# design.net
KiCad netlist of a schematic drawn in Altium Designer
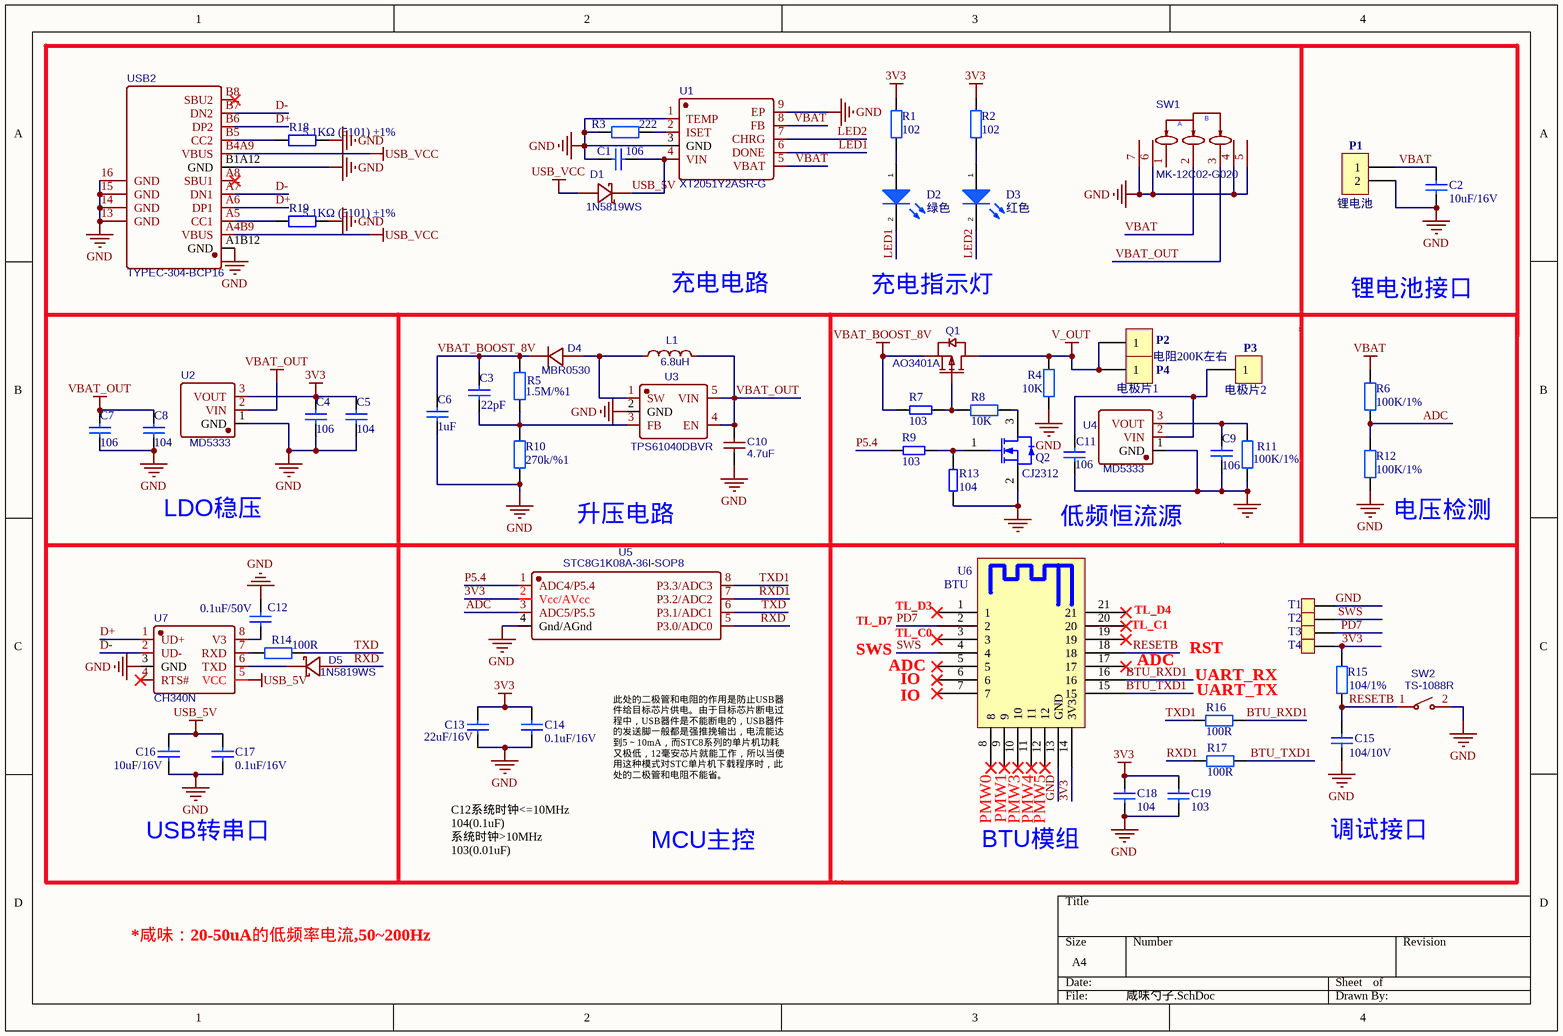
[diagram p0: 咸味勺子.SchDoc]

(export (version "E")
  (design (tool "Eeschema 10.0.6"))
  (components
    (comp (ref "C1")
      (value "106")
      (footprint "C0603")
      (description "无极性电容")
      (fields (field (name "PART NUMBER") "1.02.03.00181") (field (name "修改人") "system"))
      (libsource (lib "Database_Libs") (part "Capacitor - non polarized"))
    )
    (comp (ref "C2")
      (value "10uF/16V")
      (footprint "C0603")
      (description "无极性电容")
      (fields (field (name "PART NUMBER") "1.02.05.00869"))
      (libsource (lib "Database_Libs4") (part "Capacitor - non polarized"))
    )
    (comp (ref "C3")
      (value "22pF")
      (footprint "C0402_GRM15")
      (description "无极性电容")
      (fields (field (name "PART NUMBER") "1.02.05.00869"))
      (libsource (lib "Database_Libs4") (part "Capacitor - non polarized"))
    )
    (comp (ref "C4")
      (value "106")
      (footprint "C0603")
      (description "无极性电容")
      (fields (field (name "PART NUMBER") "1.02.05.00869"))
      (libsource (lib "Database_Libs4") (part "Capacitor - non polarized"))
    )
    (comp (ref "C5")
      (value "104")
      (footprint "C0402_GRM15")
      (description "无极性电容")
      (fields (field (name "PART NUMBER") "1.02.05.00869"))
      (libsource (lib "Database_Libs4") (part "Capacitor - non polarized"))
    )
    (comp (ref "C6")
      (value "1uF")
      (footprint "C0603")
      (description "无极性电容")
      (fields (field (name "PART NUMBER") "1.02.05.00869"))
      (libsource (lib "Database_Libs4") (part "Capacitor - non polarized"))
    )
    (comp (ref "C7")
      (value "106")
      (footprint "C0603")
      (description "无极性电容")
      (fields (field (name "PART NUMBER") "1.02.05.00869"))
      (libsource (lib "Database_Libs4") (part "Capacitor - non polarized"))
    )
    (comp (ref "C8")
      (value "104")
      (footprint "C0402_GRM15")
      (description "无极性电容")
      (fields (field (name "PART NUMBER") "1.02.05.00869"))
      (libsource (lib "Database_Libs4") (part "Capacitor - non polarized"))
    )
    (comp (ref "C9")
      (value "106")
      (footprint "C0603")
      (description "无极性电容")
      (fields (field (name "PART NUMBER") "1.02.05.00869"))
      (libsource (lib "Database_Libs4") (part "Capacitor - non polarized"))
    )
    (comp (ref "C10")
      (value "4.7uF")
      (footprint "JMK212BJ475KG-T")
      (fields
        (field (name "BOM_MANUFACTURER PART") "JMK212BJ475KG-T")
        (field (name "BOM_SUPPLIER PART") "C92788")
      )
      (libsource (lib "altium-import") (part "root_1_4.7uF_"))
    )
    (comp (ref "C11")
      (value "106")
      (footprint "C0603")
      (description "无极性电容")
      (fields (field (name "PART NUMBER") "1.02.05.00869"))
      (libsource (lib "Database_Libs4") (part "Capacitor - non polarized"))
    )
    (comp (ref "C12")
      (value "0.1uF/50V")
      (footprint "C0402_GRM15")
      (description "无极性电容")
      (fields (field (name "PART NUMBER") "1.02.05.00834") (field (name "修改人") "system"))
      (libsource (lib "Database_Libs") (part "Capacitor - non polarized"))
    )
    (comp (ref "C13")
      (value "22uF/16V")
      (footprint "C0603")
      (description "无极性电容")
      (fields (field (name "PART NUMBER") "1.02.03.00181") (field (name "修改人") "system"))
      (libsource (lib "Database_Libs") (part "Capacitor - non polarized"))
    )
    (comp (ref "C14")
      (value "0.1uF/16V")
      (footprint "C0402_GRM15")
      (description "无极性电容")
      (fields (field (name "PART NUMBER") "1.02.05.00834") (field (name "修改人") "system"))
      (libsource (lib "Database_Libs") (part "Capacitor - non polarized"))
    )
    (comp (ref "C15")
      (value "104/10V")
      (footprint "C0402_GRM15")
      (description "无极性电容")
      (fields (field (name "PART NUMBER") "1.02.05.00869"))
      (libsource (lib "Database_Libs4") (part "Capacitor - non polarized"))
    )
    (comp (ref "C16")
      (value "10uF/16V")
      (footprint "C0603")
      (description "无极性电容")
      (fields (field (name "PART NUMBER") "1.02.03.00181") (field (name "修改人") "system"))
      (libsource (lib "Database_Libs") (part "Capacitor - non polarized"))
    )
    (comp (ref "C17")
      (value "0.1uF/16V")
      (footprint "C0402_GRM15")
      (description "无极性电容")
      (fields (field (name "PART NUMBER") "1.02.05.00834") (field (name "修改人") "system"))
      (libsource (lib "Database_Libs") (part "Capacitor - non polarized"))
    )
    (comp (ref "C18")
      (value "104")
      (footprint "C0402_GRM15")
      (description "无极性电容")
      (fields (field (name "PART NUMBER") "1.02.05.00869"))
      (libsource (lib "Database_Libs4") (part "Capacitor - non polarized"))
    )
    (comp (ref "C19")
      (value "103")
      (footprint "C0402_GRM15")
      (description "无极性电容")
      (fields (field (name "PART NUMBER") "1.02.05.00869"))
      (libsource (lib "Database_Libs4") (part "Capacitor - non polarized"))
    )
    (comp (ref "D1")
      (value "1N5819WS")
      (footprint "1N5819WS")
      (fields (field (name "BOM_SUPPLIER PART") "C1884554") (field (name "CONTRIBUTOR") "LCSC"))
      (libsource (lib "altium-import") (part "root_2_1N5819WS_C1884554_"))
    )
    (comp (ref "D2")
      (value "绿色")
      (footprint "OSR50603C1E")
      (description "LED")
      (fields (field (name "PART NUMBER") "1.06.02.00452"))
      (libsource (lib "Database_Libs4") (part "LED"))
    )
    (comp (ref "D3")
      (value "红色")
      (footprint "OSR50603C1E")
      (description "LED")
      (fields (field (name "PART NUMBER") "1.06.02.00452"))
      (libsource (lib "Database_Libs4") (part "LED"))
    )
    (comp (ref "D4")
      (value "MBR0530")
      (footprint "MBR0530")
      (fields (field (name "BOM_SUPPLIER PART") "C475718") (field (name "CONTRIBUTOR") "LCSC"))
      (libsource (lib "altium-import") (part "root_0_MBR0530_C475718_"))
    )
    (comp (ref "D5")
      (value "1N5819WS")
      (footprint "SOD-323")
      (fields (field (name "BOM_SUPPLIER PART") "C1884554") (field (name "CONTRIBUTOR") "LCSC"))
      (libsource (lib "altium-import") (part "root_0_1N5819WS_C1884554_"))
    )
    (comp (ref "L1")
      (value "6.8uH")
      (footprint "CDRH3D23NP-6R8PC")
      (fields
        (field (name "BOM_SUPPLIER PART") "C323532")
        (field (name "BOM_MANUFACTURER PART") "CDRH3D23NP-6R8PC")
        (field (name "CONTRIBUTOR") "LCSC")
      )
      (libsource (lib "altium-import") (part "root_0_6.8uH_"))
    )
    (comp (ref "P1")
      (value "锂电池")
      (footprint "1.5mm 2p接插件")
      (description "Connector")
      (libsource (lib "*") (part "CON2"))
    )
    (comp (ref "P2") (value "CON1") (footprint "焊点1") (libsource (lib "智能烧水壶 -电源板") (part "CON1")))
    (comp (ref "P3") (value "CON1") (footprint "焊点1") (libsource (lib "智能烧水壶 -电源板") (part "CON1")))
    (comp (ref "P4") (value "CON1") (footprint "焊点1") (libsource (lib "智能烧水壶 -电源板") (part "CON1")))
    (comp (ref "Q1")
      (value "AO3401A")
      (footprint "AO3401A")
      (fields (field (name "BOM_SUPPLIER PART") "C700954") (field (name "CONTRIBUTOR") "LCSC"))
      (libsource (lib "altium-import") (part "root_1_mirrored_AO3401A_C700954_"))
    )
    (comp (ref "Q2")
      (value "CJ2312")
      (footprint "CJ2312")
      (description "N-Channel MOSFET")
      (fields
        (field (name "PART NUMBER") "1.06.11.00008")
        (field (name "ORCAD LIBRARY PATH") "‪Z:\\tuya_lib\\sch-lib\\DISCRETE.OLB")
        (field (name "修改人") "system")
      )
      (libsource (lib "Database_Libs") (part "MOSFET-N"))
    )
    (comp (ref "R1")
      (value "102")
      (footprint "R0402")
      (description "电阻")
      (fields (field (name "PART NUMBER") "1.01.01.00808"))
      (libsource (lib "Database_Libs4") (part "Resistor"))
    )
    (comp (ref "R2")
      (value "102")
      (footprint "R0402")
      (description "电阻")
      (fields (field (name "PART NUMBER") "1.01.01.00808"))
      (libsource (lib "Database_Libs4") (part "Resistor"))
    )
    (comp (ref "R3")
      (value "222")
      (footprint "R0402")
      (description "电阻")
      (fields (field (name "PART NUMBER") "1.01.01.00808"))
      (libsource (lib "") (part "Resistor_1"))
    )
    (comp (ref "R4")
      (value "10K")
      (footprint "R0402")
      (description "电阻")
      (libsource (lib "Database_Libs") (part "Resistor"))
    )
    (comp (ref "R5")
      (value "1.5M/%1")
      (footprint "R0402")
      (description "电阻")
      (libsource (lib "") (part "Resistor_1"))
    )
    (comp (ref "R6")
      (value "100K/1%")
      (footprint "R0402")
      (description "电阻")
      (libsource (lib "") (part "Resistor_1"))
    )
    (comp (ref "R7")
      (value "103")
      (footprint "R0402")
      (description "RES")
      (libsource (lib "先锋器件封装库") (part "RES-1"))
    )
    (comp (ref "R8")
      (value "10K")
      (footprint "R0402")
      (description "电阻")
      (libsource (lib "") (part "Resistor_2"))
    )
    (comp (ref "R9")
      (value "103")
      (footprint "R0402")
      (description "RES")
      (libsource (lib "先锋器件封装库") (part "RES-1"))
    )
    (comp (ref "R10")
      (value "270k/%1")
      (footprint "R0402")
      (description "电阻")
      (libsource (lib "") (part "Resistor_1"))
    )
    (comp (ref "R11")
      (value "100K/1%")
      (footprint "R0402")
      (description "电阻")
      (libsource (lib "") (part "Resistor_1"))
    )
    (comp (ref "R12")
      (value "100K/1%")
      (footprint "R0402")
      (description "电阻")
      (libsource (lib "") (part "Resistor_1"))
    )
    (comp (ref "R13")
      (value "104")
      (footprint "R0402")
      (description "RES")
      (libsource (lib "先锋器件封装库") (part "RES-1"))
    )
    (comp (ref "R14")
      (value "100R")
      (footprint "R0402")
      (description "电阻")
      (fields (field (name "PART NUMBER") "1.01.01.00808") (field (name "修改人") "system"))
      (libsource (lib "") (part "Resistor_2"))
    )
    (comp (ref "R15")
      (value "104/1%")
      (footprint "R0402")
      (description "电阻")
      (fields (field (name "PART NUMBER") "1.01.01.00808"))
      (libsource (lib "Database_Libs4") (part "Resistor"))
    )
    (comp (ref "R16")
      (value "100R")
      (footprint "R0402")
      (description "电阻")
      (fields (field (name "PART NUMBER") "1.01.01.00808"))
      (libsource (lib "") (part "Resistor_1"))
    )
    (comp (ref "R17")
      (value "100R")
      (footprint "R0402")
      (description "电阻")
      (fields (field (name "PART NUMBER") "1.01.01.00808"))
      (libsource (lib "") (part "Resistor_1"))
    )
    (comp (ref "R18")
      (value "5.1KΩ (5101) ±1%")
      (footprint "0603_R")
      (description "贴片电阻")
      (libsource (lib "Miscellaneous Devices LC") (part "0603 5.1KΩ (5101) 1%"))
    )
    (comp (ref "R19")
      (value "5.1KΩ (5101) ±1%")
      (footprint "0603_R")
      (description "贴片电阻")
      (libsource (lib "Miscellaneous Devices LC") (part "0603 5.1KΩ (5101) 1%"))
    )
    (comp (ref "SW1")
      (value "MK-12C02-G020")
      (footprint "SW-SMD_MK-12C02-G020")
      (fields (field (name "BOM_SUPPLIER PART") "C963206") (field (name "CONTRIBUTOR") "LCSC"))
      (libsource (lib "MYSCH") (part "SW-MK-12C02-G020"))
    )
    (comp (ref "SW2")
      (value "TS-1088R")
      (footprint "TS-1088R-02026")
      (fields
        (field (name "BOM_SUPPLIER PART") "C455280")
        (field (name "BOM_MANUFACTURER PART") "TS-1088R-02026")
        (field (name "CONTRIBUTOR") "LCSC")
      )
      (libsource (lib "altium-import") (part "root_0_TS-1088R-02026_"))
    )
    (comp (ref "T1") (value "TP") (footprint "TP1") (libsource (lib "MIAXIS-SCH") (part "TP")))
    (comp (ref "T2") (value "TP") (footprint "TP1") (libsource (lib "MIAXIS-SCH") (part "TP")))
    (comp (ref "T3") (value "TP") (footprint "TP1") (libsource (lib "MIAXIS-SCH") (part "TP")))
    (comp (ref "T4") (value "TP") (footprint "TP1") (libsource (lib "MIAXIS-SCH") (part "TP")))
    (comp (ref "U1")
      (value "XT2051Y2ASR-G")
      (footprint "XT2051Y2ASR-G")
      (fields (field (name "BOM_SUPPLIER PART") "C236398") (field (name "CONTRIBUTOR") "LCSC"))
      (libsource (lib "altium-import") (part "root_0_XT2051Y2ASR-G_"))
    )
    (comp (ref "U2")
      (value "MD5333")
      (footprint "MD5333")
      (fields (field (name "BOM_SUPPLIER PART") "C2827936") (field (name "CONTRIBUTOR") "LCSC"))
      (libsource (lib "altium-import") (part "root_2_MD5333_"))
    )
    (comp (ref "U3")
      (value "TPS61040DBVR")
      (footprint "TPS61040DBVR")
      (fields (field (name "BOM_SUPPLIER PART") "C7722"))
      (libsource (lib "altium-import") (part "root_0_TPS61040DBVR_"))
    )
    (comp (ref "U4")
      (value "MD5333")
      (footprint "MD5333")
      (fields (field (name "BOM_SUPPLIER PART") "C2827936") (field (name "CONTRIBUTOR") "LCSC"))
      (libsource (lib "altium-import") (part "root_2_MD5333_"))
    )
    (comp (ref "U5")
      (value "STC8G1K08A-36I-SOP8")
      (footprint "STC8G1K08A-36I-SOP8")
      (fields (field (name "BOM_SUPPLIER PART") "C915663") (field (name "CONTRIBUTOR") "LCSC"))
      (libsource (lib "altium-import") (part "root_0_STC8G1K08A-36I-SOP8_"))
    )
    (comp (ref "U6")
      (value "BTU")
      (footprint "CBU1")
      (fields (field (name "PART NUMBER") "0110"))
      (libsource (lib "BTU_V100") (part "CBU"))
    )
    (comp (ref "U7")
      (value "CH340N")
      (footprint "CH340N")
      (fields (field (name "BOM_SUPPLIER PART") "C506813") (field (name "CONTRIBUTOR") "LCSC"))
      (libsource (lib "TY") (part "CH340N"))
    )
    (comp (ref "USB2")
      (value "TYPEC-304-BCP16")
      (footprint "USB-C-SMD_TYPEC-304-BCP16")
      (fields (field (name "BOM_SUPPLIER PART") "C720629") (field (name "CONTRIBUTOR") "LCSC"))
      (libsource (lib "MYSCH") (part "TYPEC-304-BCP16"))
    )
  )
  (nets
    (net (code "1") (name "/ADC") (class "Default")
      (node (ref "R12") (pin "2") (pinfunction "2_2") (pintype "passive"))
      (node (ref "R6") (pin "1") (pinfunction "1_1") (pintype "passive"))
      (node (ref "U5") (pin "3") (pinfunction "ADC5/P5.5_3") (pintype "passive"))
    )
    (net (code "2") (name "/BTU_RXD1") (class "Default")
      (node (ref "R16") (pin "1") (pinfunction "1_1") (pintype "passive"))
      (node (ref "U6") (pin "16") (pinfunction "16_16") (pintype "passive"))
    )
    (net (code "3") (name "/BTU_TXD1") (class "Default")
      (node (ref "R17") (pin "1") (pinfunction "1_1") (pintype "passive"))
      (node (ref "U6") (pin "15") (pinfunction "15_15") (pintype "passive"))
    )
    (net (code "4") (name "/D+") (class "Default")
      (node (ref "U7") (pin "1") (pinfunction "UD+_1") (pintype "passive"))
      (node (ref "USB2") (pin "A6") (pinfunction "DP1_A6") (pintype "passive"))
      (node (ref "USB2") (pin "B6") (pinfunction "DP2_B6") (pintype "passive"))
    )
    (net (code "5") (name "/D-") (class "Default")
      (node (ref "U7") (pin "2") (pinfunction "UD-_2") (pintype "passive"))
      (node (ref "USB2") (pin "A7") (pinfunction "DN1_A7") (pintype "passive"))
      (node (ref "USB2") (pin "B7") (pinfunction "DN2_B7") (pintype "passive"))
    )
    (net (code "6") (name "/LED1") (class "Default")
      (node (ref "D2") (pin "2") (pinfunction "2_2") (pintype "passive"))
      (node (ref "U1") (pin "6") (pinfunction "DONE_6") (pintype "passive"))
    )
    (net (code "7") (name "/LED2") (class "Default")
      (node (ref "D3") (pin "2") (pinfunction "2_2") (pintype "passive"))
      (node (ref "U1") (pin "7") (pinfunction "CHRG_7") (pintype "passive"))
    )
    (net (code "8") (name "/P5.4") (class "Default")
      (node (ref "R9") (pin "1") (pintype "passive"))
      (node (ref "U5") (pin "1") (pinfunction "ADC4/P5.4_1") (pintype "passive"))
    )
    (net (code "9") (name "/PD7") (class "Default")
      (node (ref "T3") (pin "1") (pinfunction "1_1") (pintype "passive"))
      (node (ref "U6") (pin "2") (pinfunction "2_2") (pintype "passive"))
    )
    (net (code "10") (name "/RESETB") (class "Default")
      (node (ref "C15") (pin "1") (pinfunction "1_1") (pintype "passive"))
      (node (ref "R15") (pin "1") (pinfunction "1_1") (pintype "passive"))
      (node (ref "SW2") (pin "1") (pinfunction "1_1") (pintype "passive"))
      (node (ref "U6") (pin "18") (pinfunction "18_18") (pintype "passive"))
    )
    (net (code "11") (name "/RXD") (class "Default")
      (node (ref "D5") (pin "2") (pinfunction "A_2") (pintype "passive"))
      (node (ref "U5") (pin "5") (pinfunction "P3.0/ADC0_5") (pintype "passive"))
    )
    (net (code "12") (name "/RXD1") (class "Default")
      (node (ref "R17") (pin "2") (pinfunction "2_2") (pintype "passive"))
      (node (ref "U5") (pin "7") (pinfunction "P3.2/ADC2_7") (pintype "passive"))
    )
    (net (code "13") (name "/SWS") (class "Default")
      (node (ref "T2") (pin "1") (pinfunction "1_1") (pintype "passive"))
      (node (ref "U6") (pin "4") (pinfunction "4_4") (pintype "passive"))
    )
    (net (code "14") (name "/TXD") (class "Default")
      (node (ref "R14") (pin "2") (pinfunction "2_2") (pintype "passive"))
      (node (ref "U5") (pin "6") (pinfunction "P3.1/ADC1_6") (pintype "passive"))
    )
    (net (code "15") (name "/TXD1") (class "Default")
      (node (ref "R16") (pin "2") (pinfunction "2_2") (pintype "passive"))
      (node (ref "U5") (pin "8") (pinfunction "P3.3/ADC3_8") (pintype "passive"))
    )
    (net (code "16") (name "3V3") (class "Default")
      (node (ref "C13") (pin "2") (pinfunction "2_2") (pintype "passive"))
      (node (ref "C14") (pin "2") (pinfunction "2_2") (pintype "passive"))
      (node (ref "C18") (pin "1") (pinfunction "1_1") (pintype "passive"))
      (node (ref "C19") (pin "1") (pinfunction "1_1") (pintype "passive"))
      (node (ref "C4") (pin "1") (pinfunction "1_1") (pintype "passive"))
      (node (ref "C5") (pin "1") (pinfunction "1_1") (pintype "passive"))
      (node (ref "R1") (pin "2") (pinfunction "2_2") (pintype "passive"))
      (node (ref "R15") (pin "2") (pinfunction "2_2") (pintype "passive"))
      (node (ref "R2") (pin "2") (pinfunction "2_2") (pintype "passive"))
      (node (ref "T4") (pin "1") (pinfunction "1_1") (pintype "passive"))
      (node (ref "U2") (pin "3") (pinfunction "VOUT_3") (pintype "passive"))
      (node (ref "U5") (pin "2") (pinfunction "Vcc/AVcc_2") (pintype "passive"))
      (node (ref "U6") (pin "14") (pinfunction "3V3_14") (pintype "passive"))
    )
    (net (code "17") (name "GND") (class "Default")
      (node (ref "C1") (pin "2") (pinfunction "2_2") (pintype "passive"))
      (node (ref "C10") (pin "1") (pinfunction "1_1") (pintype "passive"))
      (node (ref "C11") (pin "2") (pinfunction "2_2") (pintype "passive"))
      (node (ref "C12") (pin "2") (pinfunction "2_2") (pintype "passive"))
      (node (ref "C13") (pin "1") (pinfunction "1_1") (pintype "passive"))
      (node (ref "C14") (pin "1") (pinfunction "1_1") (pintype "passive"))
      (node (ref "C15") (pin "2") (pinfunction "2_2") (pintype "passive"))
      (node (ref "C16") (pin "1") (pinfunction "1_1") (pintype "passive"))
      (node (ref "C17") (pin "1") (pinfunction "1_1") (pintype "passive"))
      (node (ref "C18") (pin "2") (pinfunction "2_2") (pintype "passive"))
      (node (ref "C19") (pin "2") (pinfunction "2_2") (pintype "passive"))
      (node (ref "C2") (pin "2") (pinfunction "2_2") (pintype "passive"))
      (node (ref "C4") (pin "2") (pinfunction "2_2") (pintype "passive"))
      (node (ref "C5") (pin "2") (pinfunction "2_2") (pintype "passive"))
      (node (ref "C6") (pin "2") (pinfunction "2_2") (pintype "passive"))
      (node (ref "C7") (pin "2") (pinfunction "2_2") (pintype "passive"))
      (node (ref "C8") (pin "2") (pinfunction "2_2") (pintype "passive"))
      (node (ref "C9") (pin "2") (pinfunction "2_2") (pintype "passive"))
      (node (ref "P1") (pin "2") (pinfunction "2_2") (pintype "passive"))
      (node (ref "Q2") (pin "2") (pinfunction "S_2") (pintype "passive"))
      (node (ref "R10") (pin "1") (pinfunction "1_1") (pintype "passive"))
      (node (ref "R11") (pin "1") (pinfunction "1_1") (pintype "passive"))
      (node (ref "R12") (pin "1") (pinfunction "1_1") (pintype "passive"))
      (node (ref "R13") (pin "1") (pintype "passive"))
      (node (ref "R18") (pin "2") (pinfunction "2_2") (pintype "passive"))
      (node (ref "R19") (pin "2") (pinfunction "2_2") (pintype "passive"))
      (node (ref "R3") (pin "2") (pinfunction "2_2") (pintype "passive"))
      (node (ref "R4") (pin "2") (pinfunction "2_2") (pintype "passive"))
      (node (ref "SW1") (pin "4") (pinfunction "4_4") (pintype "passive"))
      (node (ref "SW1") (pin "5") (pinfunction "5_5") (pintype "passive"))
      (node (ref "SW1") (pin "6") (pinfunction "6_6") (pintype "passive"))
      (node (ref "SW1") (pin "7") (pinfunction "7_7") (pintype "passive"))
      (node (ref "SW2") (pin "2") (pinfunction "2_2") (pintype "passive"))
      (node (ref "T1") (pin "1") (pinfunction "1_1") (pintype "passive"))
      (node (ref "U1") (pin "1") (pinfunction "TEMP_1") (pintype "passive"))
      (node (ref "U1") (pin "3") (pinfunction "GND_3") (pintype "passive"))
      (node (ref "U1") (pin "9") (pinfunction "EP_9") (pintype "passive"))
      (node (ref "U2") (pin "1") (pinfunction "GND_1") (pintype "passive"))
      (node (ref "U3") (pin "2") (pinfunction "GND_2") (pintype "passive"))
      (node (ref "U4") (pin "1") (pinfunction "GND_1") (pintype "passive"))
      (node (ref "U5") (pin "4") (pinfunction "Gnd/AGnd_4") (pintype "passive"))
      (node (ref "U6") (pin "13") (pinfunction "GND_13") (pintype "passive"))
      (node (ref "U7") (pin "3") (pinfunction "GND_3") (pintype "passive"))
      (node (ref "USB2") (pin "13") (pinfunction "GND_13") (pintype "passive"))
      (node (ref "USB2") (pin "14") (pinfunction "GND_14") (pintype "passive"))
      (node (ref "USB2") (pin "15") (pinfunction "GND_15") (pintype "passive"))
      (node (ref "USB2") (pin "16") (pinfunction "GND_16") (pintype "passive"))
      (node (ref "USB2") (pin "A1B12") (pinfunction "GND_A1B12") (pintype "passive"))
      (node (ref "USB2") (pin "B1A12") (pinfunction "GND_B1A12") (pintype "passive"))
    )
    (net (code "18") (name "Net-(D2-Pad1)") (class "Default")
      (node (ref "D2") (pin "1") (pinfunction "1_1") (pintype "passive"))
      (node (ref "R1") (pin "1") (pinfunction "1_1") (pintype "passive"))
    )
    (net (code "19") (name "Net-(D3-Pad1)") (class "Default")
      (node (ref "D3") (pin "1") (pinfunction "1_1") (pintype "passive"))
      (node (ref "R2") (pin "1") (pinfunction "1_1") (pintype "passive"))
    )
    (net (code "20") (name "Net-(D4-A)") (class "Default")
      (node (ref "D4") (pin "2") (pinfunction "A_2") (pintype "passive"))
      (node (ref "L1") (pin "1") (pinfunction "1_1") (pintype "passive"))
      (node (ref "U3") (pin "1") (pinfunction "SW_1") (pintype "passive"))
    )
    (net (code "21") (name "Net-(D5-C)") (class "Default")
      (node (ref "D5") (pin "1") (pinfunction "C_1") (pintype "passive"))
      (node (ref "U7") (pin "6") (pinfunction "TXD_6") (pintype "passive"))
    )
    (net (code "22") (name "Net-(Q1-G)") (class "Default")
      (node (ref "Q1") (pin "1") (pinfunction "G_1") (pintype "passive"))
      (node (ref "R7") (pin "2") (pintype "passive"))
      (node (ref "R8") (pin "1") (pinfunction "1_1") (pintype "passive"))
    )
    (net (code "23") (name "Net-(Q2-D)") (class "Default")
      (node (ref "Q2") (pin "3") (pinfunction "D_3") (pintype "passive"))
      (node (ref "R8") (pin "2") (pinfunction "2_2") (pintype "passive"))
    )
    (net (code "24") (name "Net-(Q2-G)") (class "Default")
      (node (ref "Q2") (pin "1") (pinfunction "G_1") (pintype "passive"))
      (node (ref "R13") (pin "2") (pintype "passive"))
      (node (ref "R9") (pin "2") (pintype "passive"))
    )
    (net (code "25") (name "Net-(U1-ISET)") (class "Default")
      (node (ref "R3") (pin "1") (pinfunction "1_1") (pintype "passive"))
      (node (ref "U1") (pin "2") (pinfunction "ISET_2") (pintype "passive"))
    )
    (net (code "26") (name "Net-(U3-FB)") (class "Default")
      (node (ref "C3") (pin "2") (pinfunction "2_2") (pintype "passive"))
      (node (ref "R10") (pin "2") (pinfunction "2_2") (pintype "passive"))
      (node (ref "R5") (pin "1") (pinfunction "1_1") (pintype "passive"))
      (node (ref "U3") (pin "3") (pinfunction "FB_3") (pintype "passive"))
    )
    (net (code "27") (name "Net-(U4-VIN)") (class "Default")
      (node (ref "C11") (pin "1") (pinfunction "1_1") (pintype "passive"))
      (node (ref "P3") (pin "1") (pinfunction "1_1") (pintype "passive"))
      (node (ref "U4") (pin "2") (pinfunction "VIN_2") (pintype "passive"))
    )
    (net (code "28") (name "Net-(U4-VOUT)") (class "Default")
      (node (ref "C9") (pin "1") (pinfunction "1_1") (pintype "passive"))
      (node (ref "R11") (pin "2") (pinfunction "2_2") (pintype "passive"))
      (node (ref "U4") (pin "3") (pinfunction "VOUT_3") (pintype "passive"))
    )
    (net (code "29") (name "Net-(U7-RXD)") (class "Default")
      (node (ref "R14") (pin "1") (pinfunction "1_1") (pintype "passive"))
      (node (ref "U7") (pin "7") (pinfunction "RXD_7") (pintype "passive"))
    )
    (net (code "30") (name "Net-(U7-V3)") (class "Default")
      (node (ref "C12") (pin "1") (pinfunction "1_1") (pintype "passive"))
      (node (ref "U7") (pin "8") (pinfunction "V3_8") (pintype "passive"))
    )
    (net (code "31") (name "Net-(USB2-CC1)") (class "Default")
      (node (ref "R19") (pin "1") (pinfunction "1_1") (pintype "passive"))
      (node (ref "USB2") (pin "A5") (pinfunction "CC1_A5") (pintype "passive"))
    )
    (net (code "32") (name "Net-(USB2-CC2)") (class "Default")
      (node (ref "R18") (pin "1") (pinfunction "1_1") (pintype "passive"))
      (node (ref "USB2") (pin "B5") (pinfunction "CC2_B5") (pintype "passive"))
    )
    (net (code "33") (name "USB_5V") (class "Default")
      (node (ref "C1") (pin "1") (pinfunction "1_1") (pintype "passive"))
      (node (ref "C16") (pin "2") (pinfunction "2_2") (pintype "passive"))
      (node (ref "C17") (pin "2") (pinfunction "2_2") (pintype "passive"))
      (node (ref "D1") (pin "1") (pinfunction "C_1") (pintype "passive"))
      (node (ref "U1") (pin "4") (pinfunction "VIN_4") (pintype "passive"))
      (node (ref "U7") (pin "5") (pinfunction "VCC_5") (pintype "passive"))
    )
    (net (code "34") (name "USB_VCC") (class "Default")
      (node (ref "D1") (pin "2") (pinfunction "A_2") (pintype "passive"))
      (node (ref "USB2") (pin "A4B9") (pinfunction "VBUS_A4B9") (pintype "passive"))
      (node (ref "USB2") (pin "B4A9") (pinfunction "VBUS_B4A9") (pintype "passive"))
    )
    (net (code "35") (name "VBAT") (class "Default")
      (node (ref "C2") (pin "1") (pinfunction "1_1") (pintype "passive"))
      (node (ref "P1") (pin "1") (pinfunction "1_1") (pintype "passive"))
      (node (ref "R6") (pin "2") (pinfunction "2_2") (pintype "passive"))
      (node (ref "SW1") (pin "2") (pinfunction "2_2") (pintype "passive"))
      (node (ref "U1") (pin "5") (pinfunction "VBAT_5") (pintype "passive"))
      (node (ref "U1") (pin "8") (pinfunction "FB_8") (pintype "passive"))
    )
    (net (code "36") (name "VBAT_BOOST_8V") (class "Default")
      (node (ref "C3") (pin "1") (pinfunction "1_1") (pintype "passive"))
      (node (ref "C6") (pin "1") (pinfunction "1_1") (pintype "passive"))
      (node (ref "D4") (pin "1") (pinfunction "K_1") (pintype "passive"))
      (node (ref "Q1") (pin "2") (pinfunction "S_2") (pintype "passive"))
      (node (ref "R5") (pin "2") (pinfunction "2_2") (pintype "passive"))
      (node (ref "R7") (pin "1") (pintype "passive"))
    )
    (net (code "37") (name "VBAT_OUT") (class "Default")
      (node (ref "C10") (pin "2") (pinfunction "2_2") (pintype "passive"))
      (node (ref "C7") (pin "1") (pinfunction "1_1") (pintype "passive"))
      (node (ref "C8") (pin "1") (pinfunction "1_1") (pintype "passive"))
      (node (ref "L1") (pin "2") (pinfunction "2_2") (pintype "passive"))
      (node (ref "SW1") (pin "3") (pinfunction "3_3") (pintype "passive"))
      (node (ref "U2") (pin "2") (pinfunction "VIN_2") (pintype "passive"))
      (node (ref "U3") (pin "4") (pinfunction "EN_4") (pintype "passive"))
      (node (ref "U3") (pin "5") (pinfunction "VIN_5") (pintype "passive"))
    )
    (net (code "38") (name "V_OUT") (class "Default")
      (node (ref "P2") (pin "1") (pinfunction "1_1") (pintype "passive"))
      (node (ref "P4") (pin "1") (pinfunction "1_1") (pintype "passive"))
      (node (ref "Q1") (pin "3") (pinfunction "D_3") (pintype "passive"))
      (node (ref "R4") (pin "1") (pinfunction "1_1") (pintype "passive"))
    )
    (net (code "39") (name "unconnected-(SW1-Pad1)") (class "Default")
      (node (ref "SW1") (pin "1") (pinfunction "1_1") (pintype "passive"))
    )
    (net (code "40") (name "unconnected-(U6-Pad1)") (class "Default")
      (node (ref "U6") (pin "1") (pinfunction "1_1") (pintype "passive+no_connect"))
    )
    (net (code "41") (name "unconnected-(U6-Pad3)") (class "Default")
      (node (ref "U6") (pin "3") (pinfunction "3_3") (pintype "passive+no_connect"))
    )
    (net (code "42") (name "unconnected-(U6-Pad5)") (class "Default")
      (node (ref "U6") (pin "5") (pinfunction "5_5") (pintype "passive+no_connect"))
    )
    (net (code "43") (name "unconnected-(U6-Pad6)") (class "Default")
      (node (ref "U6") (pin "6") (pinfunction "6_6") (pintype "passive+no_connect"))
    )
    (net (code "44") (name "unconnected-(U6-Pad7)") (class "Default")
      (node (ref "U6") (pin "7") (pinfunction "7_7") (pintype "passive+no_connect"))
    )
    (net (code "45") (name "unconnected-(U6-Pad8)") (class "Default")
      (node (ref "U6") (pin "8") (pinfunction "8_8") (pintype "passive+no_connect"))
    )
    (net (code "46") (name "unconnected-(U6-Pad9)") (class "Default")
      (node (ref "U6") (pin "9") (pinfunction "9_9") (pintype "passive+no_connect"))
    )
    (net (code "47") (name "unconnected-(U6-Pad10)") (class "Default")
      (node (ref "U6") (pin "10") (pinfunction "10_10") (pintype "passive+no_connect"))
    )
    (net (code "48") (name "unconnected-(U6-Pad11)") (class "Default")
      (node (ref "U6") (pin "11") (pinfunction "11_11") (pintype "passive+no_connect"))
    )
    (net (code "49") (name "unconnected-(U6-Pad12)") (class "Default")
      (node (ref "U6") (pin "12") (pinfunction "12_12") (pintype "passive+no_connect"))
    )
    (net (code "50") (name "unconnected-(U6-Pad17)") (class "Default")
      (node (ref "U6") (pin "17") (pinfunction "17_17") (pintype "passive+no_connect"))
    )
    (net (code "51") (name "unconnected-(U6-Pad19)") (class "Default")
      (node (ref "U6") (pin "19") (pinfunction "19_19") (pintype "passive+no_connect"))
    )
    (net (code "52") (name "unconnected-(U6-Pad20)") (class "Default")
      (node (ref "U6") (pin "20") (pinfunction "20_20") (pintype "passive+no_connect"))
    )
    (net (code "53") (name "unconnected-(U6-Pad21)") (class "Default")
      (node (ref "U6") (pin "21") (pinfunction "21_21") (pintype "passive+no_connect"))
    )
    (net (code "54") (name "unconnected-(U7-RTS#-Pad4)") (class "Default")
      (node (ref "U7") (pin "4") (pinfunction "RTS#_4") (pintype "passive+no_connect"))
    )
    (net (code "55") (name "unconnected-(USB2-SBU1-PadA8)") (class "Default")
      (node (ref "USB2") (pin "A8") (pinfunction "SBU1_A8") (pintype "passive+no_connect"))
    )
    (net (code "56") (name "unconnected-(USB2-SBU2-PadB8)") (class "Default")
      (node (ref "USB2") (pin "B8") (pinfunction "SBU2_B8") (pintype "passive+no_connect"))
    )
  )
)
